# 1_High_Power.net
KiCad netlist of a schematic drawn in Altium Designer
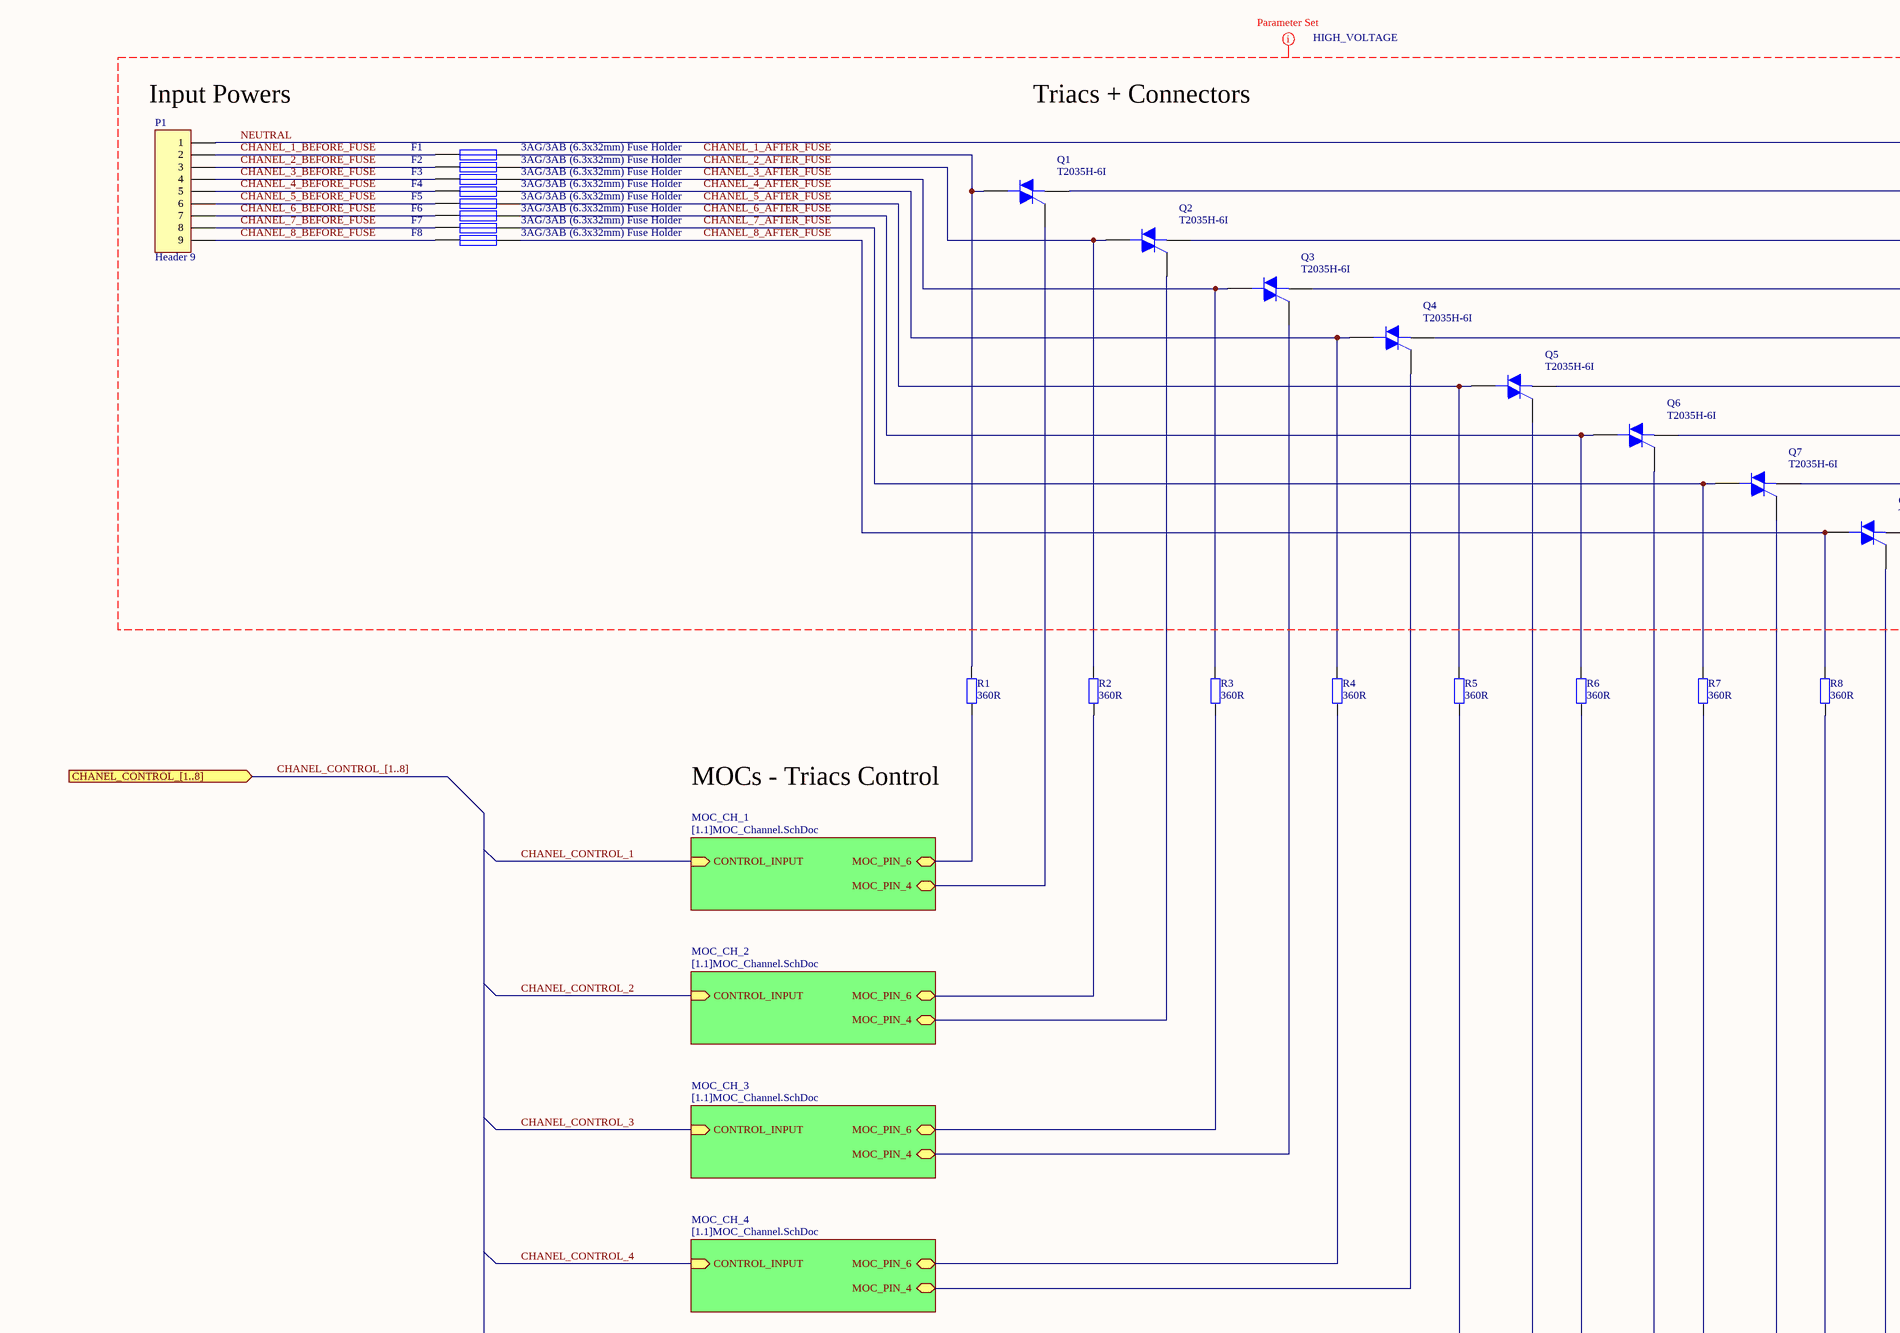
[diagram p0: [1]High_Power.SchDoc, top left]
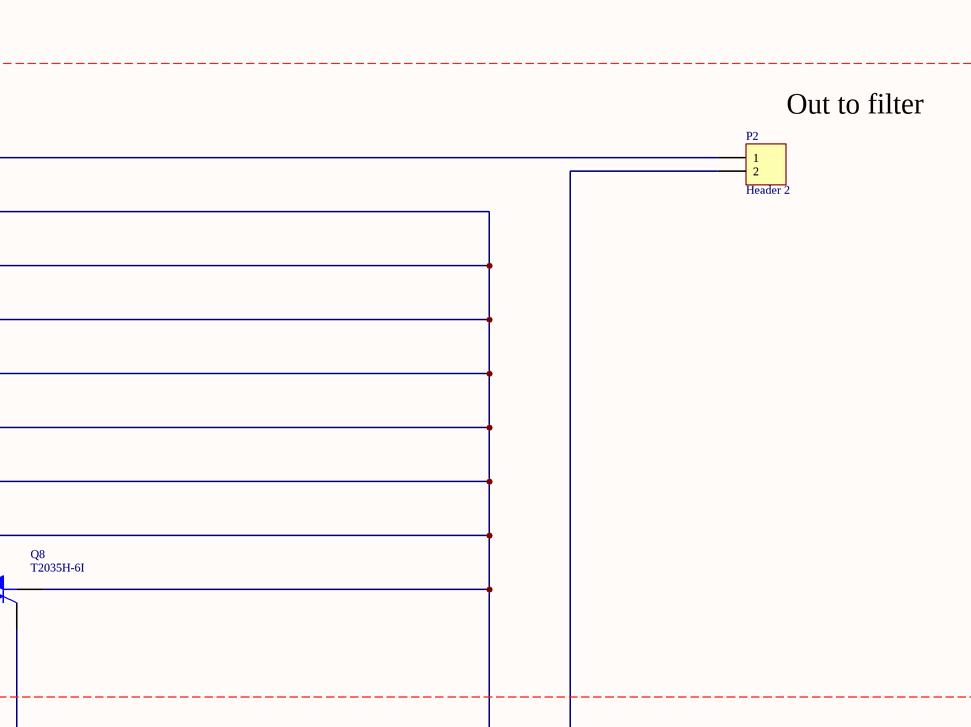
[diagram p1: [1]High_Power.SchDoc, top right]
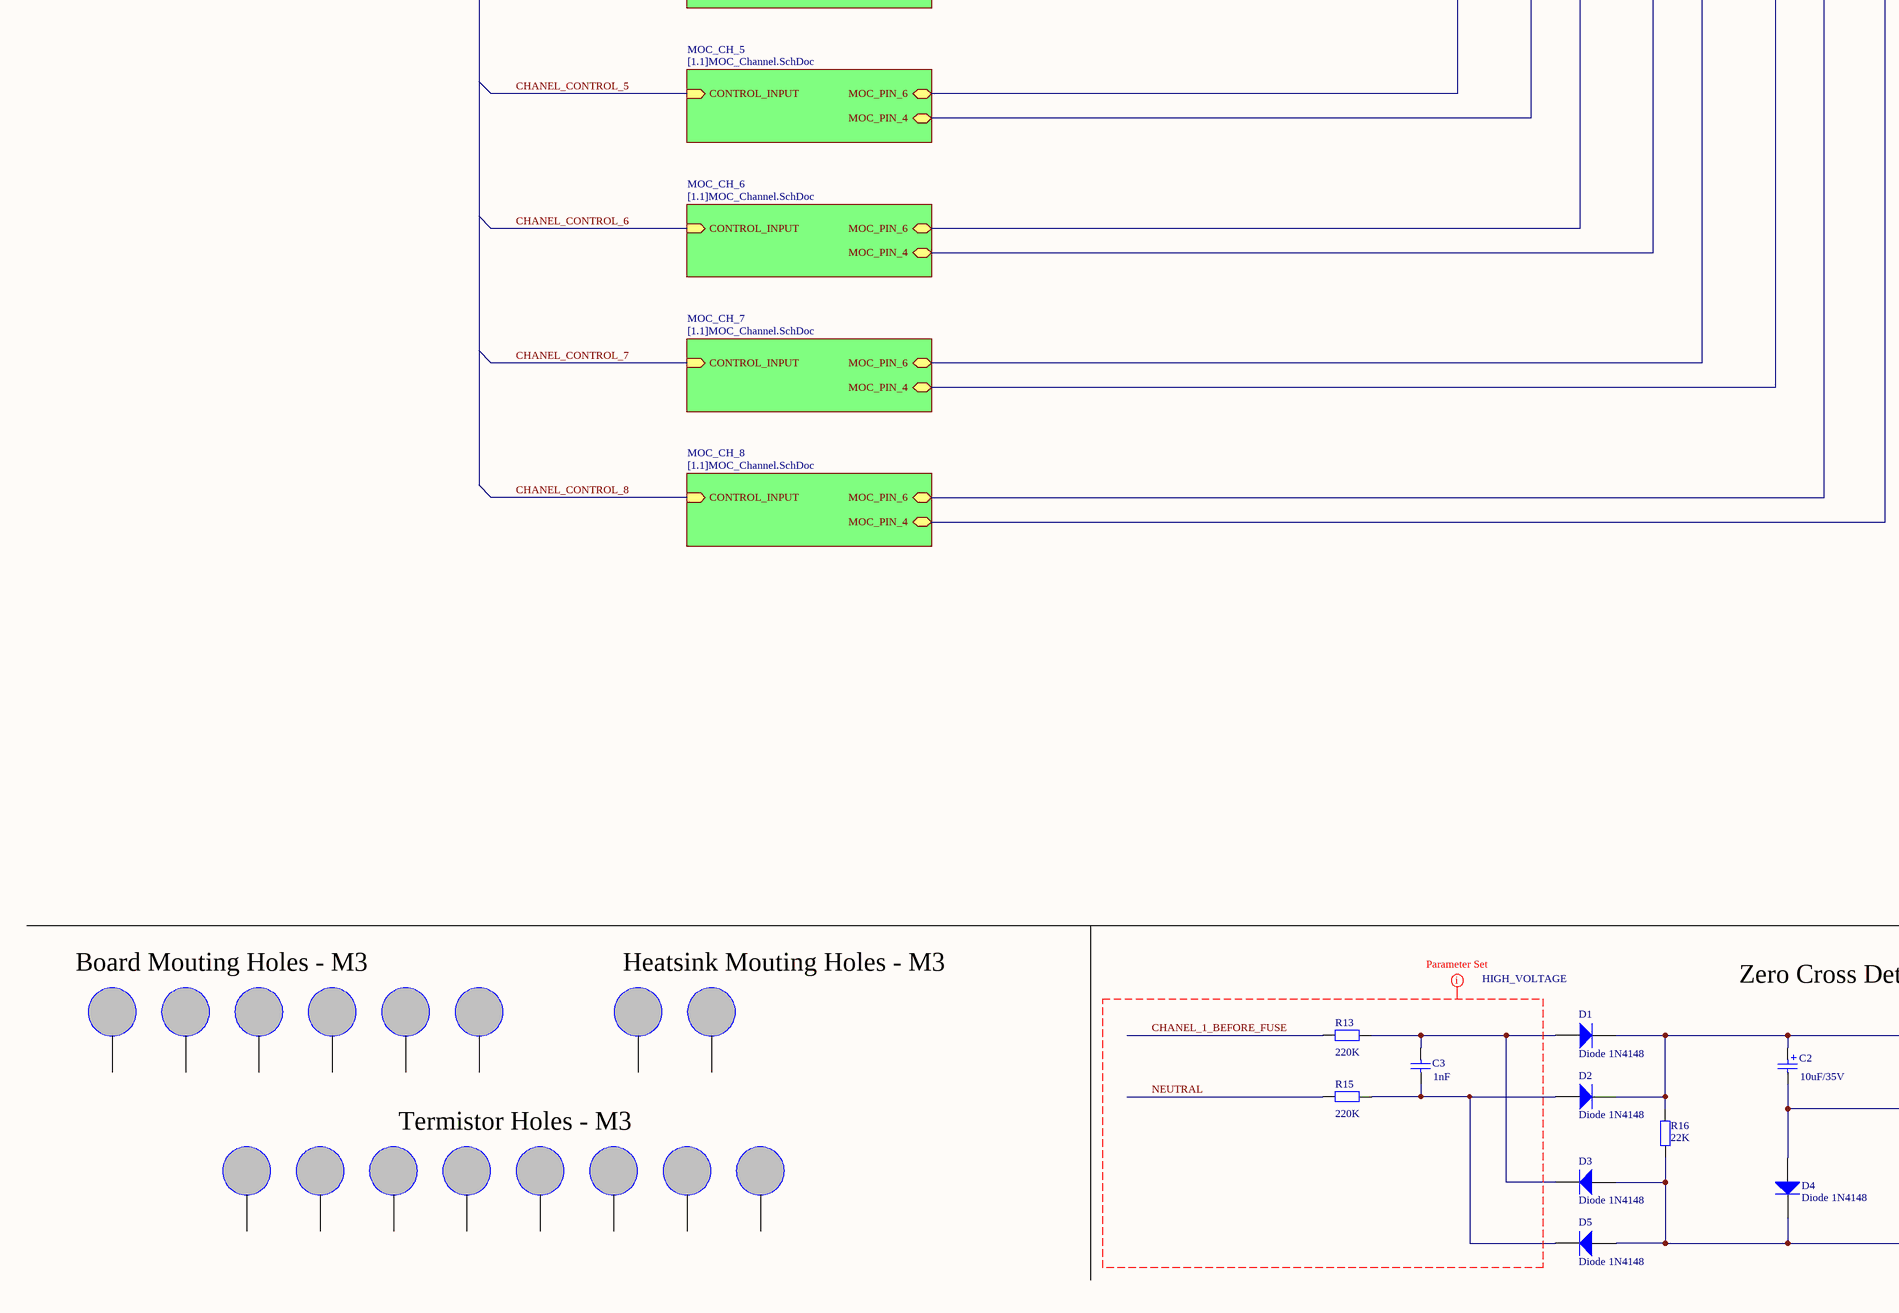
[diagram p2: [1]High_Power.SchDoc, bottom left]
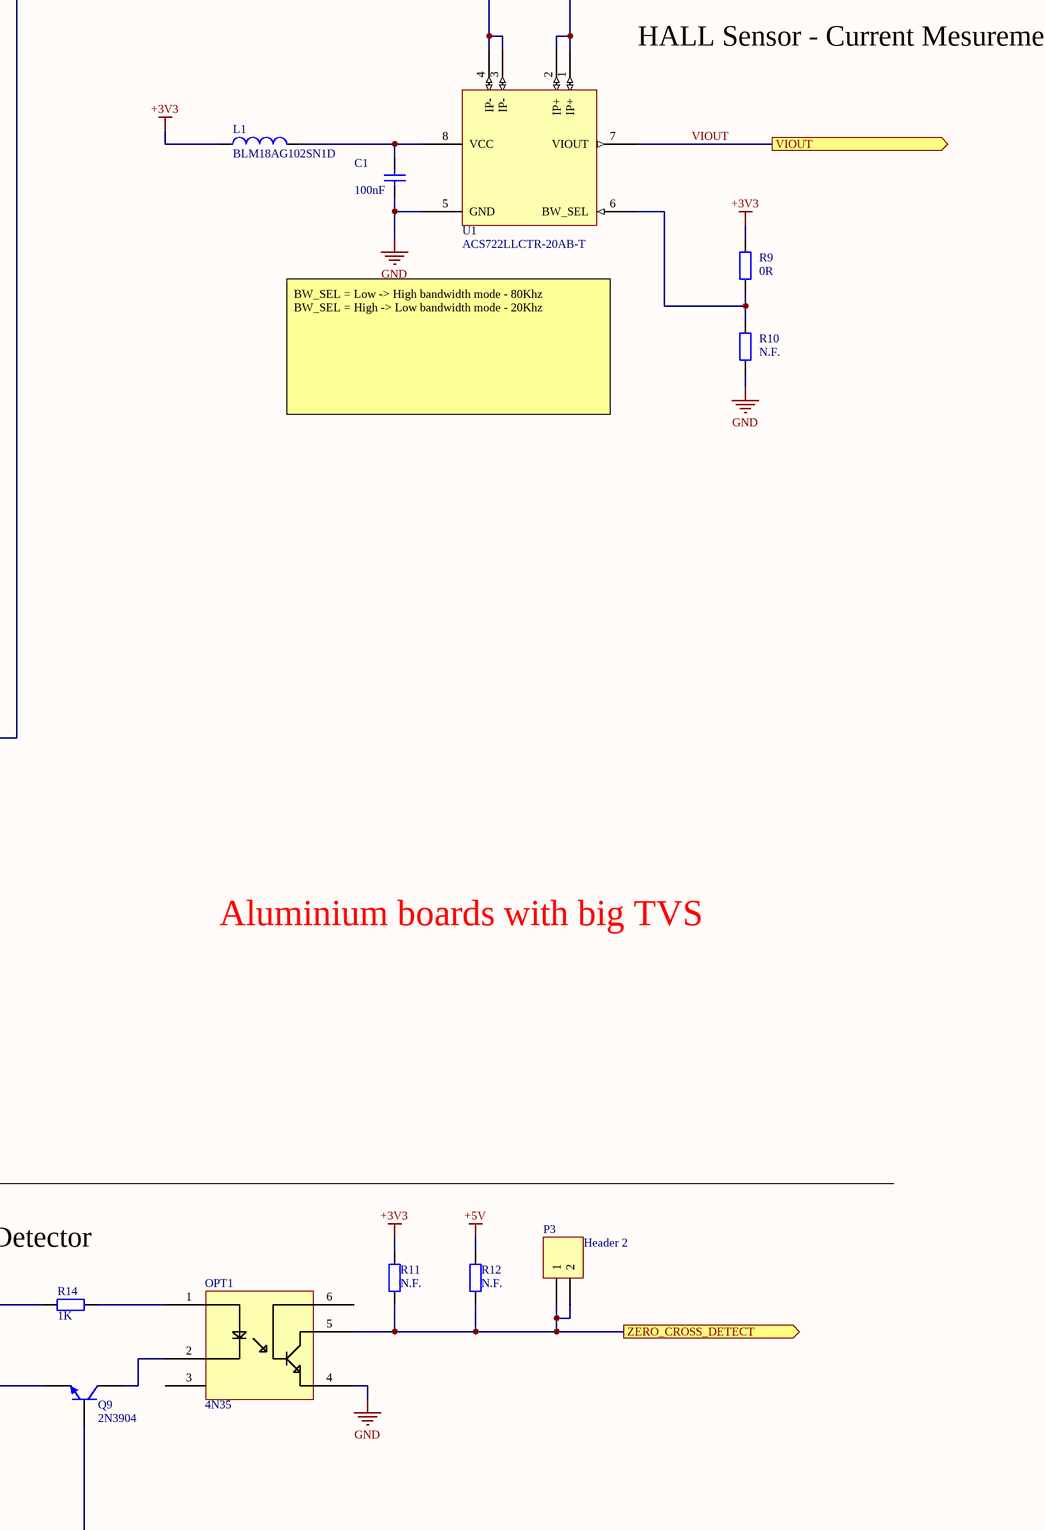
[diagram p3: [1]High_Power.SchDoc, bottom right]

(export (version "E")
  (design (tool "Eeschema 10.0.6"))
  (components
    (comp (ref "C1")
      (value "100nF")
      (footprint "1608[0603]")
      (description "Capacitor")
      (fields (field (name "Comment") "0603") (field (name "PUBLISHER") "Altium Limited"))
      (libsource (lib "Miscellaneous Devices") (part "Cap"))
    )
    (comp (ref "C2")
      (value "10uF/35V")
      (footprint "WCAP-ATG5 Capacitor")
      (description "Polarized Capacitor (Axial)")
      (fields
        (field (name "MANUFACTURER PART NO.") "860010572002")
        (field (name "Comment") "Cap Pol2")
        (field (name "PUBLISHER") "Altium Limited")
      )
      (libsource (lib "Miscellaneous Devices") (part "Cap Pol2"))
    )
    (comp (ref "C3")
      (value "1nF")
      (footprint "R82 Capacitors")
      (description "Capacitor")
      (fields
        (field (name "MANUFACTURER PART NO.") "R82EC1100SH50J")
        (field (name "Comment") "0603")
        (field (name "PUBLISHER") "Altium Limited")
      )
      (libsource (lib "Miscellaneous Devices") (part "Cap"))
    )
    (comp (ref "D1")
      (value "Diode 1N4148")
      (footprint "DO-35")
      (description "High Conductance Fast Diode")
      (fields (field (name "MANUFACTURER PART NO.") "1N4148") (field (name "PUBLISHER") "Altium Limited"))
      (libsource (lib "Miscellaneous Devices") (part "Diode 1N4148"))
    )
    (comp (ref "D2")
      (value "Diode 1N4148")
      (footprint "DO-35")
      (description "High Conductance Fast Diode")
      (fields (field (name "MANUFACTURER PART NO.") "1N4148") (field (name "PUBLISHER") "Altium Limited"))
      (libsource (lib "Miscellaneous Devices") (part "Diode 1N4148"))
    )
    (comp (ref "D3")
      (value "Diode 1N4148")
      (footprint "DO-35")
      (description "High Conductance Fast Diode")
      (fields (field (name "MANUFACTURER PART NO.") "1N4148") (field (name "PUBLISHER") "Altium Limited"))
      (libsource (lib "Miscellaneous Devices") (part "Diode 1N4148"))
    )
    (comp (ref "D4")
      (value "Diode 1N4148")
      (footprint "DO-35")
      (description "High Conductance Fast Diode")
      (fields (field (name "MANUFACTURER PART NO.") "1N4148") (field (name "PUBLISHER") "Altium Limited"))
      (libsource (lib "Miscellaneous Devices") (part "Diode 1N4148"))
    )
    (comp (ref "D5")
      (value "Diode 1N4148")
      (footprint "DO-35")
      (description "High Conductance Fast Diode")
      (fields (field (name "MANUFACTURER PART NO.") "1N4148") (field (name "PUBLISHER") "Altium Limited"))
      (libsource (lib "Miscellaneous Devices") (part "Diode 1N4148"))
    )
    (comp (ref "F1")
      (value "3AG/3AB (6.3x32mm) Fuse Holder")
      (footprint "03540101ZXGY")
      (description "Fuse")
      (fields
        (field (name "MANUFACTURER PART NO.") "03540101ZXGY")
        (field (name "PUBLISHER") "Altium Limited")
      )
      (libsource (lib "Miscellaneous Devices") (part "Fuse 1"))
    )
    (comp (ref "F2")
      (value "3AG/3AB (6.3x32mm) Fuse Holder")
      (footprint "03540101ZXGY")
      (description "Fuse")
      (fields
        (field (name "MANUFACTURER PART NO.") "03540101ZXGY")
        (field (name "PUBLISHER") "Altium Limited")
      )
      (libsource (lib "Miscellaneous Devices") (part "Fuse 1"))
    )
    (comp (ref "F3")
      (value "3AG/3AB (6.3x32mm) Fuse Holder")
      (footprint "03540101ZXGY")
      (description "Fuse")
      (fields
        (field (name "MANUFACTURER PART NO.") "03540101ZXGY")
        (field (name "PUBLISHER") "Altium Limited")
      )
      (libsource (lib "Miscellaneous Devices") (part "Fuse 1"))
    )
    (comp (ref "F4")
      (value "3AG/3AB (6.3x32mm) Fuse Holder")
      (footprint "03540101ZXGY")
      (description "Fuse")
      (fields
        (field (name "MANUFACTURER PART NO.") "03540101ZXGY")
        (field (name "PUBLISHER") "Altium Limited")
      )
      (libsource (lib "Miscellaneous Devices") (part "Fuse 1"))
    )
    (comp (ref "F5")
      (value "3AG/3AB (6.3x32mm) Fuse Holder")
      (footprint "03540101ZXGY")
      (description "Fuse")
      (fields
        (field (name "MANUFACTURER PART NO.") "03540101ZXGY")
        (field (name "PUBLISHER") "Altium Limited")
      )
      (libsource (lib "Miscellaneous Devices") (part "Fuse 1"))
    )
    (comp (ref "F6")
      (value "3AG/3AB (6.3x32mm) Fuse Holder")
      (footprint "03540101ZXGY")
      (description "Fuse")
      (fields
        (field (name "MANUFACTURER PART NO.") "03540101ZXGY")
        (field (name "PUBLISHER") "Altium Limited")
      )
      (libsource (lib "Miscellaneous Devices") (part "Fuse 1"))
    )
    (comp (ref "F7")
      (value "3AG/3AB (6.3x32mm) Fuse Holder")
      (footprint "03540101ZXGY")
      (description "Fuse")
      (fields
        (field (name "MANUFACTURER PART NO.") "03540101ZXGY")
        (field (name "PUBLISHER") "Altium Limited")
      )
      (libsource (lib "Miscellaneous Devices") (part "Fuse 1"))
    )
    (comp (ref "F8")
      (value "3AG/3AB (6.3x32mm) Fuse Holder")
      (footprint "03540101ZXGY")
      (description "Fuse")
      (fields
        (field (name "MANUFACTURER PART NO.") "03540101ZXGY")
        (field (name "PUBLISHER") "Altium Limited")
      )
      (libsource (lib "Miscellaneous Devices") (part "Fuse 1"))
    )
    (comp (ref "L1")
      (value "BLM18AG102SN1D")
      (footprint "1608[0603]")
      (description "Inductor")
      (libsource (lib "Miscellaneous Devices") (part "Inductor"))
    )
    (comp (ref "MH1")
      (value "Mouting Hole")
      (footprint "M3 Mounting Hole")
      (libsource (lib "custom_components") (part "Mouting Hole"))
    )
    (comp (ref "MH2")
      (value "Mouting Hole")
      (footprint "M3 Mounting Hole")
      (libsource (lib "custom_components") (part "Mouting Hole"))
    )
    (comp (ref "MH3")
      (value "Mouting Hole")
      (footprint "M3 Mounting Hole")
      (libsource (lib "custom_components") (part "Mouting Hole"))
    )
    (comp (ref "MH4")
      (value "Mouting Hole")
      (footprint "M3 Mounting Hole")
      (libsource (lib "custom_components") (part "Mouting Hole"))
    )
    (comp (ref "MH5")
      (value "Mouting Hole")
      (footprint "M3 Mounting Hole")
      (libsource (lib "custom_components") (part "Mouting Hole"))
    )
    (comp (ref "MH6")
      (value "Mouting Hole")
      (footprint "M3 Mounting Hole")
      (libsource (lib "custom_components") (part "Mouting Hole"))
    )
    (comp (ref "MH7")
      (value "Mouting Hole")
      (footprint "M3 Mounting Hole")
      (libsource (lib "custom_components") (part "Mouting Hole"))
    )
    (comp (ref "MH8")
      (value "Mouting Hole")
      (footprint "M3 Mounting Hole")
      (libsource (lib "custom_components") (part "Mouting Hole"))
    )
    (comp (ref "MH9")
      (value "Mouting Hole")
      (footprint "M3 Mounting Hole")
      (libsource (lib "custom_components") (part "Mouting Hole"))
    )
    (comp (ref "MH10")
      (value "Mouting Hole")
      (footprint "M3 Mounting Hole")
      (libsource (lib "custom_components") (part "Mouting Hole"))
    )
    (comp (ref "MH11")
      (value "Mouting Hole")
      (footprint "M3 Mounting Hole")
      (libsource (lib "custom_components") (part "Mouting Hole"))
    )
    (comp (ref "MH12")
      (value "Mouting Hole")
      (footprint "M3 Mounting Hole")
      (libsource (lib "custom_components") (part "Mouting Hole"))
    )
    (comp (ref "MH13")
      (value "Mouting Hole")
      (footprint "M3 Mounting Hole")
      (libsource (lib "custom_components") (part "Mouting Hole"))
    )
    (comp (ref "MH14")
      (value "Mouting Hole")
      (footprint "M3 Mounting Hole")
      (libsource (lib "custom_components") (part "Mouting Hole"))
    )
    (comp (ref "MH15")
      (value "Mouting Hole")
      (footprint "M3 Mounting Hole")
      (libsource (lib "custom_components") (part "Mouting Hole"))
    )
    (comp (ref "MH16")
      (value "Mouting Hole")
      (footprint "M3 Mounting Hole")
      (libsource (lib "custom_components") (part "Mouting Hole"))
    )
    (comp (ref "OPT1")
      (value "4N35")
      (footprint "DIP-6")
      (description "Optocoupler, Phototransistor Output, with Base Connection")
      (libsource (lib "ROV_Voltage_Switch") (part "4N35"))
    )
    (comp (ref "P1")
      (value "Header 9")
      (footprint "Phoenix Contact 1732351")
      (description "Header, 9-Pin")
      (fields
        (field (name "MANUFACTURER PART NO.") "Phoenix Contact")
        (field (name "PUBLISHER") "Altium Limited")
      )
      (libsource (lib "Miscellaneous Connectors") (part "Header 9"))
    )
    (comp (ref "P2")
      (value "Header 2")
      (footprint "Phoenix Contact 1731721")
      (description "Header, 2-Pin")
      (fields (field (name "MANUFACTURER PART NO.") "1732351") (field (name "PUBLISHER") "Altium Limited"))
      (libsource (lib "") (part "Header 2_1"))
    )
    (comp (ref "P3")
      (value "Header 2")
      (footprint "HDR1X2")
      (description "Header, 2-Pin")
      (fields (field (name "PUBLISHER") "Altium Limited"))
      (libsource (lib "Miscellaneous Connectors") (part "Header 2"))
    )
    (comp (ref "Q1")
      (value "T2035H-6I")
      (footprint "TO-220 +3D")
      (description "Silicon Bidirectional Triode Thyristor")
      (fields (field (name "PUBLISHER") "Altium Limited"))
      (libsource (lib "Miscellaneous Devices") (part "Triac"))
    )
    (comp (ref "Q2")
      (value "T2035H-6I")
      (footprint "TO-220 +3D")
      (description "Silicon Bidirectional Triode Thyristor")
      (fields (field (name "PUBLISHER") "Altium Limited"))
      (libsource (lib "Miscellaneous Devices") (part "Triac"))
    )
    (comp (ref "Q3")
      (value "T2035H-6I")
      (footprint "TO-220 +3D")
      (description "Silicon Bidirectional Triode Thyristor")
      (fields (field (name "PUBLISHER") "Altium Limited"))
      (libsource (lib "Miscellaneous Devices") (part "Triac"))
    )
    (comp (ref "Q4")
      (value "T2035H-6I")
      (footprint "TO-220 +3D")
      (description "Silicon Bidirectional Triode Thyristor")
      (fields (field (name "PUBLISHER") "Altium Limited"))
      (libsource (lib "Miscellaneous Devices") (part "Triac"))
    )
    (comp (ref "Q5")
      (value "T2035H-6I")
      (footprint "TO-220 +3D")
      (description "Silicon Bidirectional Triode Thyristor")
      (fields (field (name "PUBLISHER") "Altium Limited"))
      (libsource (lib "Miscellaneous Devices") (part "Triac"))
    )
    (comp (ref "Q6")
      (value "T2035H-6I")
      (footprint "TO-220 +3D")
      (description "Silicon Bidirectional Triode Thyristor")
      (fields (field (name "PUBLISHER") "Altium Limited"))
      (libsource (lib "Miscellaneous Devices") (part "Triac"))
    )
    (comp (ref "Q7")
      (value "T2035H-6I")
      (footprint "TO-220 +3D")
      (description "Silicon Bidirectional Triode Thyristor")
      (fields (field (name "PUBLISHER") "Altium Limited"))
      (libsource (lib "Miscellaneous Devices") (part "Triac"))
    )
    (comp (ref "Q8")
      (value "T2035H-6I")
      (footprint "TO-220 +3D")
      (description "Silicon Bidirectional Triode Thyristor")
      (fields (field (name "PUBLISHER") "Altium Limited"))
      (libsource (lib "Miscellaneous Devices") (part "Triac"))
    )
    (comp (ref "Q9")
      (value "2N3904")
      (footprint "TO-92A")
      (description "NPN General Purpose Amplifier")
      (fields (field (name "PUBLISHER") "Altium Limited"))
      (libsource (lib "Miscellaneous Devices") (part "2N3904"))
    )
    (comp (ref "R1")
      (value "360R")
      (footprint "AXIAL-0.4")
      (description "Resistor")
      (fields (field (name "Comment") "Res2") (field (name "PUBLISHER") "Altium Limited"))
      (libsource (lib "") (part "Res2_1"))
    )
    (comp (ref "R2")
      (value "360R")
      (footprint "AXIAL-0.4")
      (description "Resistor")
      (fields (field (name "Comment") "Res2") (field (name "PUBLISHER") "Altium Limited"))
      (libsource (lib "") (part "Res2_1"))
    )
    (comp (ref "R3")
      (value "360R")
      (footprint "AXIAL-0.4")
      (description "Resistor")
      (fields (field (name "Comment") "Res2") (field (name "PUBLISHER") "Altium Limited"))
      (libsource (lib "") (part "Res2_1"))
    )
    (comp (ref "R4")
      (value "360R")
      (footprint "AXIAL-0.4")
      (description "Resistor")
      (fields (field (name "Comment") "Res2") (field (name "PUBLISHER") "Altium Limited"))
      (libsource (lib "") (part "Res2_1"))
    )
    (comp (ref "R5")
      (value "360R")
      (footprint "AXIAL-0.4")
      (description "Resistor")
      (fields (field (name "Comment") "Res2") (field (name "PUBLISHER") "Altium Limited"))
      (libsource (lib "") (part "Res2_1"))
    )
    (comp (ref "R6")
      (value "360R")
      (footprint "AXIAL-0.4")
      (description "Resistor")
      (fields (field (name "Comment") "Res2") (field (name "PUBLISHER") "Altium Limited"))
      (libsource (lib "") (part "Res2_1"))
    )
    (comp (ref "R7")
      (value "360R")
      (footprint "AXIAL-0.4")
      (description "Resistor")
      (fields (field (name "Comment") "Res2") (field (name "PUBLISHER") "Altium Limited"))
      (libsource (lib "") (part "Res2_1"))
    )
    (comp (ref "R8")
      (value "360R")
      (footprint "AXIAL-0.4")
      (description "Resistor")
      (fields (field (name "Comment") "Res2") (field (name "PUBLISHER") "Altium Limited"))
      (libsource (lib "") (part "Res2_1"))
    )
    (comp (ref "R9")
      (value "0R")
      (footprint "J1-0603")
      (description "Resistor")
      (fields (field (name "Comment") "0603") (field (name "PUBLISHER") "Altium Limited"))
      (libsource (lib "") (part "Res2_1"))
    )
    (comp (ref "R10")
      (value "N.F.")
      (footprint "J1-0603")
      (description "Resistor")
      (fields (field (name "Comment") "0603") (field (name "PUBLISHER") "Altium Limited"))
      (libsource (lib "") (part "Res2_1"))
    )
    (comp (ref "R11")
      (value "N.F.")
      (footprint "J1-0603")
      (description "Resistor")
      (fields (field (name "Comment") "0603") (field (name "PUBLISHER") "Altium Limited"))
      (libsource (lib "") (part "Res2_3"))
    )
    (comp (ref "R12")
      (value "N.F.")
      (footprint "J1-0603")
      (description "Resistor")
      (fields (field (name "Comment") "0603") (field (name "PUBLISHER") "Altium Limited"))
      (libsource (lib "") (part "Res2_3"))
    )
    (comp (ref "R13")
      (value "220K")
      (footprint "AXIAL-0.4")
      (description "Resistor")
      (fields (field (name "Comment") "Res2") (field (name "PUBLISHER") "Altium Limited"))
      (libsource (lib "") (part "Res2_2"))
    )
    (comp (ref "R14")
      (value "1K")
      (footprint "AXIAL-0.4")
      (description "Resistor")
      (fields (field (name "Comment") "Res2") (field (name "PUBLISHER") "Altium Limited"))
      (libsource (lib "Miscellaneous Devices") (part "Res2"))
    )
    (comp (ref "R15")
      (value "220K")
      (footprint "AXIAL-0.4")
      (description "Resistor")
      (fields (field (name "Comment") "Res2") (field (name "PUBLISHER") "Altium Limited"))
      (libsource (lib "") (part "Res2_2"))
    )
    (comp (ref "R16")
      (value "22K")
      (footprint "AXIAL-0.4")
      (description "Resistor")
      (fields (field (name "Comment") "Res2") (field (name "PUBLISHER") "Altium Limited"))
      (libsource (lib "") (part "Res2_1"))
    )
    (comp (ref "U1")
      (value "ACS722LLCTR-20AB-T")
      (footprint "SOIC127P600-8CL")
      (description "High-Accuracy, Galvanically Isolated Current Sensor IC\r\nwith Small Footprint SOIC8 Package")
      (libsource (lib "ROV_Voltage_Switch") (part "ACS723"))
    )
  )
  (nets
    (net (code "1") (name "+3V3") (class "Default")
      (node (ref "L1") (pin "1") (pinfunction "1_1") (pintype "passive"))
      (node (ref "R11") (pin "1") (pinfunction "1_1") (pintype "passive"))
      (node (ref "R9") (pin "2") (pinfunction "2_2") (pintype "passive"))
    )
    (net (code "2") (name "+5V") (class "Default")
      (node (ref "R12") (pin "1") (pinfunction "1_1") (pintype "passive"))
    )
    (net (code "3") (name "/CHANEL_1_AFTER_FUSE") (class "Default")
      (node (ref "F1") (pin "2") (pinfunction "2_2") (pintype "passive"))
      (node (ref "Q1") (pin "2") (pinfunction "M2_2") (pintype "passive"))
      (node (ref "R1") (pin "2") (pinfunction "2_2") (pintype "passive"))
    )
    (net (code "4") (name "/CHANEL_1_BEFORE_FUSE") (class "Default")
      (node (ref "F1") (pin "1") (pinfunction "1_1") (pintype "passive"))
      (node (ref "P1") (pin "2") (pinfunction "2_2") (pintype "passive"))
      (node (ref "R13") (pin "1") (pinfunction "1_1") (pintype "passive"))
    )
    (net (code "5") (name "/CHANEL_2_AFTER_FUSE") (class "Default")
      (node (ref "F2") (pin "2") (pinfunction "2_2") (pintype "passive"))
      (node (ref "Q2") (pin "2") (pinfunction "M2_2") (pintype "passive"))
      (node (ref "R2") (pin "2") (pinfunction "2_2") (pintype "passive"))
    )
    (net (code "6") (name "/CHANEL_2_BEFORE_FUSE") (class "Default")
      (node (ref "F2") (pin "1") (pinfunction "1_1") (pintype "passive"))
      (node (ref "P1") (pin "3") (pinfunction "3_3") (pintype "passive"))
    )
    (net (code "7") (name "/CHANEL_3_AFTER_FUSE") (class "Default")
      (node (ref "F3") (pin "2") (pinfunction "2_2") (pintype "passive"))
      (node (ref "Q3") (pin "2") (pinfunction "M2_2") (pintype "passive"))
      (node (ref "R3") (pin "2") (pinfunction "2_2") (pintype "passive"))
    )
    (net (code "8") (name "/CHANEL_3_BEFORE_FUSE") (class "Default")
      (node (ref "F3") (pin "1") (pinfunction "1_1") (pintype "passive"))
      (node (ref "P1") (pin "4") (pinfunction "4_4") (pintype "passive"))
    )
    (net (code "9") (name "/CHANEL_4_AFTER_FUSE") (class "Default")
      (node (ref "F4") (pin "2") (pinfunction "2_2") (pintype "passive"))
      (node (ref "Q4") (pin "2") (pinfunction "M2_2") (pintype "passive"))
      (node (ref "R4") (pin "2") (pinfunction "2_2") (pintype "passive"))
    )
    (net (code "10") (name "/CHANEL_4_BEFORE_FUSE") (class "Default")
      (node (ref "F4") (pin "1") (pinfunction "1_1") (pintype "passive"))
      (node (ref "P1") (pin "5") (pinfunction "5_5") (pintype "passive"))
    )
    (net (code "11") (name "/CHANEL_5_AFTER_FUSE") (class "Default")
      (node (ref "F5") (pin "2") (pinfunction "2_2") (pintype "passive"))
      (node (ref "Q5") (pin "2") (pinfunction "M2_2") (pintype "passive"))
      (node (ref "R5") (pin "2") (pinfunction "2_2") (pintype "passive"))
    )
    (net (code "12") (name "/CHANEL_5_BEFORE_FUSE") (class "Default")
      (node (ref "F5") (pin "1") (pinfunction "1_1") (pintype "passive"))
      (node (ref "P1") (pin "6") (pinfunction "6_6") (pintype "passive"))
    )
    (net (code "13") (name "/CHANEL_6_AFTER_FUSE") (class "Default")
      (node (ref "F6") (pin "2") (pinfunction "2_2") (pintype "passive"))
      (node (ref "Q6") (pin "2") (pinfunction "M2_2") (pintype "passive"))
      (node (ref "R6") (pin "2") (pinfunction "2_2") (pintype "passive"))
    )
    (net (code "14") (name "/CHANEL_6_BEFORE_FUSE") (class "Default")
      (node (ref "F6") (pin "1") (pinfunction "1_1") (pintype "passive"))
      (node (ref "P1") (pin "7") (pinfunction "7_7") (pintype "passive"))
    )
    (net (code "15") (name "/CHANEL_7_AFTER_FUSE") (class "Default")
      (node (ref "F7") (pin "2") (pinfunction "2_2") (pintype "passive"))
      (node (ref "Q7") (pin "2") (pinfunction "M2_2") (pintype "passive"))
      (node (ref "R7") (pin "2") (pinfunction "2_2") (pintype "passive"))
    )
    (net (code "16") (name "/CHANEL_7_BEFORE_FUSE") (class "Default")
      (node (ref "F7") (pin "1") (pinfunction "1_1") (pintype "passive"))
      (node (ref "P1") (pin "8") (pinfunction "8_8") (pintype "passive"))
    )
    (net (code "17") (name "/CHANEL_8_AFTER_FUSE") (class "Default")
      (node (ref "F8") (pin "2") (pinfunction "2_2") (pintype "passive"))
      (node (ref "Q8") (pin "2") (pinfunction "M2_2") (pintype "passive"))
      (node (ref "R8") (pin "2") (pinfunction "2_2") (pintype "passive"))
    )
    (net (code "18") (name "/CHANEL_8_BEFORE_FUSE") (class "Default")
      (node (ref "F8") (pin "1") (pinfunction "1_1") (pintype "passive"))
      (node (ref "P1") (pin "9") (pinfunction "9_9") (pintype "passive"))
    )
    (net (code "28") (name "/MOC_PIN_4") (class "Default")
      (node (ref "Q6") (pin "3") (pinfunction "G_3") (pintype "passive"))
    )
    (net (code "29") (name "/MOC_PIN_4_1") (class "Default")
      (node (ref "Q8") (pin "3") (pinfunction "G_3") (pintype "passive"))
    )
    (net (code "30") (name "/MOC_PIN_4_2") (class "Default")
      (node (ref "Q4") (pin "3") (pinfunction "G_3") (pintype "passive"))
    )
    (net (code "31") (name "/MOC_PIN_4_3") (class "Default")
      (node (ref "Q1") (pin "3") (pinfunction "G_3") (pintype "passive"))
    )
    (net (code "32") (name "/MOC_PIN_4_4") (class "Default")
      (node (ref "Q3") (pin "3") (pinfunction "G_3") (pintype "passive"))
    )
    (net (code "33") (name "/MOC_PIN_4_5") (class "Default")
      (node (ref "Q7") (pin "3") (pinfunction "G_3") (pintype "passive"))
    )
    (net (code "34") (name "/MOC_PIN_4_6") (class "Default")
      (node (ref "Q2") (pin "3") (pinfunction "G_3") (pintype "passive"))
    )
    (net (code "35") (name "/MOC_PIN_4_7") (class "Default")
      (node (ref "Q5") (pin "3") (pinfunction "G_3") (pintype "passive"))
    )
    (net (code "36") (name "/MOC_PIN_6") (class "Default")
      (node (ref "R8") (pin "1") (pinfunction "1_1") (pintype "passive"))
    )
    (net (code "37") (name "/MOC_PIN_6_1") (class "Default")
      (node (ref "R7") (pin "1") (pinfunction "1_1") (pintype "passive"))
    )
    (net (code "38") (name "/MOC_PIN_6_2") (class "Default")
      (node (ref "R1") (pin "1") (pinfunction "1_1") (pintype "passive"))
    )
    (net (code "39") (name "/MOC_PIN_6_3") (class "Default")
      (node (ref "R2") (pin "1") (pinfunction "1_1") (pintype "passive"))
    )
    (net (code "40") (name "/MOC_PIN_6_4") (class "Default")
      (node (ref "R3") (pin "1") (pinfunction "1_1") (pintype "passive"))
    )
    (net (code "41") (name "/MOC_PIN_6_5") (class "Default")
      (node (ref "R4") (pin "1") (pinfunction "1_1") (pintype "passive"))
    )
    (net (code "42") (name "/MOC_PIN_6_6") (class "Default")
      (node (ref "R5") (pin "1") (pinfunction "1_1") (pintype "passive"))
    )
    (net (code "43") (name "/MOC_PIN_6_7") (class "Default")
      (node (ref "R6") (pin "1") (pinfunction "1_1") (pintype "passive"))
    )
    (net (code "44") (name "/NEUTRAL") (class "Default")
      (node (ref "P1") (pin "1") (pinfunction "1_1") (pintype "passive"))
      (node (ref "P2") (pin "1") (pinfunction "1_1") (pintype "passive"))
      (node (ref "R15") (pin "1") (pinfunction "1_1") (pintype "passive"))
    )
    (net (code "45") (name "/VIOUT") (class "Default")
      (node (ref "U1") (pin "7") (pinfunction "VIOUT_7") (pintype "output"))
    )
    (net (code "46") (name "/ZERO_CROSS_DETECT") (class "Default")
      (node (ref "OPT1") (pin "5") (pinfunction "C_5") (pintype "passive"))
      (node (ref "P3") (pin "1") (pinfunction "1_1") (pintype "passive"))
      (node (ref "P3") (pin "2") (pinfunction "2_2") (pintype "passive"))
      (node (ref "R11") (pin "2") (pinfunction "2_2") (pintype "passive"))
      (node (ref "R12") (pin "2") (pinfunction "2_2") (pintype "passive"))
    )
    (net (code "47") (name "GND") (class "Default")
      (node (ref "C1") (pin "1") (pinfunction "1_1") (pintype "passive"))
      (node (ref "OPT1") (pin "4") (pinfunction "E_4") (pintype "passive"))
      (node (ref "R10") (pin "1") (pinfunction "1_1") (pintype "passive"))
      (node (ref "U1") (pin "5") (pinfunction "GND_5") (pintype "power_in"))
    )
    (net (code "48") (name "Net-(D1-A)") (class "Default")
      (node (ref "C3") (pin "2") (pinfunction "2_2") (pintype "passive"))
      (node (ref "D1") (pin "1") (pinfunction "A_1") (pintype "passive"))
      (node (ref "D3") (pin "2") (pinfunction "K_2") (pintype "passive"))
      (node (ref "R13") (pin "2") (pinfunction "2_2") (pintype "passive"))
    )
    (net (code "49") (name "Net-(D1-K)") (class "Default")
      (node (ref "C2") (pin "1") (pinfunction "1_1") (pintype "passive"))
      (node (ref "D1") (pin "2") (pinfunction "K_2") (pintype "passive"))
      (node (ref "D2") (pin "2") (pinfunction "K_2") (pintype "passive"))
      (node (ref "R14") (pin "2") (pinfunction "2_2") (pintype "passive"))
      (node (ref "R16") (pin "2") (pinfunction "2_2") (pintype "passive"))
    )
    (net (code "50") (name "Net-(D2-A)") (class "Default")
      (node (ref "C3") (pin "1") (pinfunction "1_1") (pintype "passive"))
      (node (ref "D2") (pin "1") (pinfunction "A_1") (pintype "passive"))
      (node (ref "D5") (pin "2") (pinfunction "K_2") (pintype "passive"))
      (node (ref "R15") (pin "2") (pinfunction "2_2") (pintype "passive"))
    )
    (net (code "51") (name "Net-(D3-A)") (class "Default")
      (node (ref "D3") (pin "1") (pinfunction "A_1") (pintype "passive"))
      (node (ref "D4") (pin "2") (pinfunction "K_2") (pintype "passive"))
      (node (ref "D5") (pin "1") (pinfunction "A_1") (pintype "passive"))
      (node (ref "Q9") (pin "2") (pinfunction "B_2") (pintype "passive"))
      (node (ref "R16") (pin "1") (pinfunction "1_1") (pintype "passive"))
    )
    (net (code "52") (name "Net-(D4-A)") (class "Default")
      (node (ref "C2") (pin "2") (pinfunction "2_2") (pintype "passive"))
      (node (ref "D4") (pin "1") (pinfunction "A_1") (pintype "passive"))
      (node (ref "Q9") (pin "1") (pinfunction "E_1") (pintype "passive"))
    )
    (net (code "53") (name "Net-(OPT1-A)") (class "Default")
      (node (ref "OPT1") (pin "1") (pinfunction "A_1") (pintype "passive"))
      (node (ref "R14") (pin "1") (pinfunction "1_1") (pintype "passive"))
    )
    (net (code "54") (name "Net-(P2-Pad2)") (class "Default")
      (node (ref "P2") (pin "2") (pinfunction "2_2") (pintype "passive"))
      (node (ref "U1") (pin "1") (pinfunction "IP+_1") (pintype "bidirectional"))
      (node (ref "U1") (pin "2") (pinfunction "IP+_2") (pintype "bidirectional"))
    )
    (net (code "55") (name "Net-(Q1-M1)") (class "Default")
      (node (ref "Q1") (pin "1") (pinfunction "M1_1") (pintype "passive"))
      (node (ref "Q2") (pin "1") (pinfunction "M1_1") (pintype "passive"))
      (node (ref "Q3") (pin "1") (pinfunction "M1_1") (pintype "passive"))
      (node (ref "Q4") (pin "1") (pinfunction "M1_1") (pintype "passive"))
      (node (ref "Q5") (pin "1") (pinfunction "M1_1") (pintype "passive"))
      (node (ref "Q6") (pin "1") (pinfunction "M1_1") (pintype "passive"))
      (node (ref "Q7") (pin "1") (pinfunction "M1_1") (pintype "passive"))
      (node (ref "Q8") (pin "1") (pinfunction "M1_1") (pintype "passive"))
      (node (ref "U1") (pin "3") (pinfunction "IP-_3") (pintype "bidirectional"))
      (node (ref "U1") (pin "4") (pinfunction "IP-_4") (pintype "bidirectional"))
    )
    (net (code "56") (name "Net-(Q9-C)") (class "Default")
      (node (ref "OPT1") (pin "2") (pinfunction "C_2") (pintype "passive"))
      (node (ref "Q9") (pin "3") (pinfunction "C_3") (pintype "passive"))
    )
    (net (code "57") (name "Net-(U1-BW_SEL)") (class "Default")
      (node (ref "R10") (pin "2") (pinfunction "2_2") (pintype "passive"))
      (node (ref "R9") (pin "1") (pinfunction "1_1") (pintype "passive"))
      (node (ref "U1") (pin "6") (pinfunction "BW_SEL_6") (pintype "input"))
    )
    (net (code "58") (name "Net-(U1-VCC)") (class "Default")
      (node (ref "C1") (pin "2") (pinfunction "2_2") (pintype "passive"))
      (node (ref "L1") (pin "2") (pinfunction "2_2") (pintype "passive"))
      (node (ref "U1") (pin "8") (pinfunction "VCC_8") (pintype "power_in"))
    )
    (net (code "59") (name "unconnected-(MH1-Pad1)") (class "Default")
      (node (ref "MH1") (pin "1") (pinfunction "1_1") (pintype "passive"))
    )
    (net (code "60") (name "unconnected-(MH2-Pad1)") (class "Default")
      (node (ref "MH2") (pin "1") (pinfunction "1_1") (pintype "passive"))
    )
    (net (code "61") (name "unconnected-(MH3-Pad1)") (class "Default")
      (node (ref "MH3") (pin "1") (pinfunction "1_1") (pintype "passive"))
    )
    (net (code "62") (name "unconnected-(MH4-Pad1)") (class "Default")
      (node (ref "MH4") (pin "1") (pinfunction "1_1") (pintype "passive"))
    )
    (net (code "63") (name "unconnected-(MH5-Pad1)") (class "Default")
      (node (ref "MH5") (pin "1") (pinfunction "1_1") (pintype "passive"))
    )
    (net (code "64") (name "unconnected-(MH6-Pad1)") (class "Default")
      (node (ref "MH6") (pin "1") (pinfunction "1_1") (pintype "passive"))
    )
    (net (code "65") (name "unconnected-(MH7-Pad1)") (class "Default")
      (node (ref "MH7") (pin "1") (pinfunction "1_1") (pintype "passive"))
    )
    (net (code "66") (name "unconnected-(MH8-Pad1)") (class "Default")
      (node (ref "MH8") (pin "1") (pinfunction "1_1") (pintype "passive"))
    )
    (net (code "67") (name "unconnected-(MH9-Pad1)") (class "Default")
      (node (ref "MH9") (pin "1") (pinfunction "1_1") (pintype "passive"))
    )
    (net (code "68") (name "unconnected-(MH10-Pad1)") (class "Default")
      (node (ref "MH10") (pin "1") (pinfunction "1_1") (pintype "passive"))
    )
    (net (code "69") (name "unconnected-(MH11-Pad1)") (class "Default")
      (node (ref "MH11") (pin "1") (pinfunction "1_1") (pintype "passive"))
    )
    (net (code "70") (name "unconnected-(MH12-Pad1)") (class "Default")
      (node (ref "MH12") (pin "1") (pinfunction "1_1") (pintype "passive"))
    )
    (net (code "71") (name "unconnected-(MH13-Pad1)") (class "Default")
      (node (ref "MH13") (pin "1") (pinfunction "1_1") (pintype "passive"))
    )
    (net (code "72") (name "unconnected-(MH14-Pad1)") (class "Default")
      (node (ref "MH14") (pin "1") (pinfunction "1_1") (pintype "passive"))
    )
    (net (code "73") (name "unconnected-(MH15-Pad1)") (class "Default")
      (node (ref "MH15") (pin "1") (pinfunction "1_1") (pintype "passive"))
    )
    (net (code "74") (name "unconnected-(MH16-Pad1)") (class "Default")
      (node (ref "MH16") (pin "1") (pinfunction "1_1") (pintype "passive"))
    )
    (net (code "75") (name "unconnected-(OPT1-B-Pad6)") (class "Default")
      (node (ref "OPT1") (pin "6") (pinfunction "B_6") (pintype "passive"))
    )
    (net (code "76") (name "unconnected-(OPT1-NC-Pad3)") (class "Default")
      (node (ref "OPT1") (pin "3") (pinfunction "NC_3") (pintype "passive"))
    )
  )
)
